# SSOP-TSSOP28.net
KiCad netlist of a schematic drawn in Altium Designer
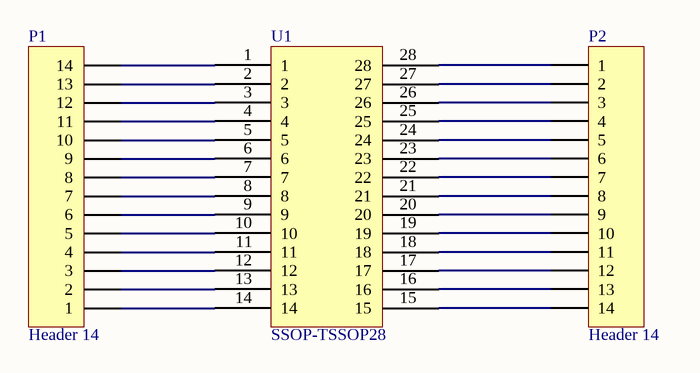
[diagram p0: SSOP-TSSOP28.SchDoc]

(export (version "E")
  (design (tool "Eeschema 10.0.6"))
  (components
    (comp (ref "P1")
      (value "Header 14")
      (footprint "HDR1X14")
      (description "Header, 14-Pin")
      (fields (field (name "PUBLISHER") "Altium Limited"))
      (libsource (lib "Miscellaneous Connectors") (part "Header 14"))
    )
    (comp (ref "P2")
      (value "Header 14")
      (footprint "HDR1X14")
      (description "Header, 14-Pin")
      (fields (field (name "PUBLISHER") "Altium Limited"))
      (libsource (lib "") (part "Header 14_1"))
    )
    (comp (ref "U1")
      (value "SSOP-TSSOP28")
      (footprint "SSOP-TSSOP28")
      (libsource (lib "PCB_Breakout_Boards") (part "SSOP-TSSOP28"))
    )
  )
  (nets
    (net (code "1") (name "Net-(P1-Pad1)") (class "Default")
      (node (ref "P1") (pin "1") (pinfunction "1_1") (pintype "passive"))
      (node (ref "U1") (pin "14") (pinfunction "14_14") (pintype "passive"))
    )
    (net (code "2") (name "Net-(P1-Pad2)") (class "Default")
      (node (ref "P1") (pin "2") (pinfunction "2_2") (pintype "passive"))
      (node (ref "U1") (pin "13") (pinfunction "13_13") (pintype "passive"))
    )
    (net (code "3") (name "Net-(P1-Pad3)") (class "Default")
      (node (ref "P1") (pin "3") (pinfunction "3_3") (pintype "passive"))
      (node (ref "U1") (pin "12") (pinfunction "12_12") (pintype "passive"))
    )
    (net (code "4") (name "Net-(P1-Pad4)") (class "Default")
      (node (ref "P1") (pin "4") (pinfunction "4_4") (pintype "passive"))
      (node (ref "U1") (pin "11") (pinfunction "11_11") (pintype "passive"))
    )
    (net (code "5") (name "Net-(P1-Pad5)") (class "Default")
      (node (ref "P1") (pin "5") (pinfunction "5_5") (pintype "passive"))
      (node (ref "U1") (pin "10") (pinfunction "10_10") (pintype "passive"))
    )
    (net (code "6") (name "Net-(P1-Pad6)") (class "Default")
      (node (ref "P1") (pin "6") (pinfunction "6_6") (pintype "passive"))
      (node (ref "U1") (pin "9") (pinfunction "9_9") (pintype "passive"))
    )
    (net (code "7") (name "Net-(P1-Pad7)") (class "Default")
      (node (ref "P1") (pin "7") (pinfunction "7_7") (pintype "passive"))
      (node (ref "U1") (pin "8") (pinfunction "8_8") (pintype "passive"))
    )
    (net (code "8") (name "Net-(P1-Pad8)") (class "Default")
      (node (ref "P1") (pin "8") (pinfunction "8_8") (pintype "passive"))
      (node (ref "U1") (pin "7") (pinfunction "7_7") (pintype "passive"))
    )
    (net (code "9") (name "Net-(P1-Pad9)") (class "Default")
      (node (ref "P1") (pin "9") (pinfunction "9_9") (pintype "passive"))
      (node (ref "U1") (pin "6") (pinfunction "6_6") (pintype "passive"))
    )
    (net (code "10") (name "Net-(P1-Pad10)") (class "Default")
      (node (ref "P1") (pin "10") (pinfunction "10_10") (pintype "passive"))
      (node (ref "U1") (pin "5") (pinfunction "5_5") (pintype "passive"))
    )
    (net (code "11") (name "Net-(P1-Pad11)") (class "Default")
      (node (ref "P1") (pin "11") (pinfunction "11_11") (pintype "passive"))
      (node (ref "U1") (pin "4") (pinfunction "4_4") (pintype "passive"))
    )
    (net (code "12") (name "Net-(P1-Pad12)") (class "Default")
      (node (ref "P1") (pin "12") (pinfunction "12_12") (pintype "passive"))
      (node (ref "U1") (pin "3") (pinfunction "3_3") (pintype "passive"))
    )
    (net (code "13") (name "Net-(P1-Pad13)") (class "Default")
      (node (ref "P1") (pin "13") (pinfunction "13_13") (pintype "passive"))
      (node (ref "U1") (pin "2") (pinfunction "2_2") (pintype "passive"))
    )
    (net (code "14") (name "Net-(P1-Pad14)") (class "Default")
      (node (ref "P1") (pin "14") (pinfunction "14_14") (pintype "passive"))
      (node (ref "U1") (pin "1") (pinfunction "1_1") (pintype "passive"))
    )
    (net (code "15") (name "Net-(P2-Pad1)") (class "Default")
      (node (ref "P2") (pin "1") (pinfunction "1_1") (pintype "passive"))
      (node (ref "U1") (pin "28") (pinfunction "28_28") (pintype "passive"))
    )
    (net (code "16") (name "Net-(P2-Pad2)") (class "Default")
      (node (ref "P2") (pin "2") (pinfunction "2_2") (pintype "passive"))
      (node (ref "U1") (pin "27") (pinfunction "27_27") (pintype "passive"))
    )
    (net (code "17") (name "Net-(P2-Pad3)") (class "Default")
      (node (ref "P2") (pin "3") (pinfunction "3_3") (pintype "passive"))
      (node (ref "U1") (pin "26") (pinfunction "26_26") (pintype "passive"))
    )
    (net (code "18") (name "Net-(P2-Pad4)") (class "Default")
      (node (ref "P2") (pin "4") (pinfunction "4_4") (pintype "passive"))
      (node (ref "U1") (pin "25") (pinfunction "25_25") (pintype "passive"))
    )
    (net (code "19") (name "Net-(P2-Pad5)") (class "Default")
      (node (ref "P2") (pin "5") (pinfunction "5_5") (pintype "passive"))
      (node (ref "U1") (pin "24") (pinfunction "24_24") (pintype "passive"))
    )
    (net (code "20") (name "Net-(P2-Pad6)") (class "Default")
      (node (ref "P2") (pin "6") (pinfunction "6_6") (pintype "passive"))
      (node (ref "U1") (pin "23") (pinfunction "23_23") (pintype "passive"))
    )
    (net (code "21") (name "Net-(P2-Pad7)") (class "Default")
      (node (ref "P2") (pin "7") (pinfunction "7_7") (pintype "passive"))
      (node (ref "U1") (pin "22") (pinfunction "22_22") (pintype "passive"))
    )
    (net (code "22") (name "Net-(P2-Pad8)") (class "Default")
      (node (ref "P2") (pin "8") (pinfunction "8_8") (pintype "passive"))
      (node (ref "U1") (pin "21") (pinfunction "21_21") (pintype "passive"))
    )
    (net (code "23") (name "Net-(P2-Pad9)") (class "Default")
      (node (ref "P2") (pin "9") (pinfunction "9_9") (pintype "passive"))
      (node (ref "U1") (pin "20") (pinfunction "20_20") (pintype "passive"))
    )
    (net (code "24") (name "Net-(P2-Pad10)") (class "Default")
      (node (ref "P2") (pin "10") (pinfunction "10_10") (pintype "passive"))
      (node (ref "U1") (pin "19") (pinfunction "19_19") (pintype "passive"))
    )
    (net (code "25") (name "Net-(P2-Pad11)") (class "Default")
      (node (ref "P2") (pin "11") (pinfunction "11_11") (pintype "passive"))
      (node (ref "U1") (pin "18") (pinfunction "18_18") (pintype "passive"))
    )
    (net (code "26") (name "Net-(P2-Pad12)") (class "Default")
      (node (ref "P2") (pin "12") (pinfunction "12_12") (pintype "passive"))
      (node (ref "U1") (pin "17") (pinfunction "17_17") (pintype "passive"))
    )
    (net (code "27") (name "Net-(P2-Pad13)") (class "Default")
      (node (ref "P2") (pin "13") (pinfunction "13_13") (pintype "passive"))
      (node (ref "U1") (pin "16") (pinfunction "16_16") (pintype "passive"))
    )
    (net (code "28") (name "Net-(P2-Pad14)") (class "Default")
      (node (ref "P2") (pin "14") (pinfunction "14_14") (pintype "passive"))
      (node (ref "U1") (pin "15") (pinfunction "15_15") (pintype "passive"))
    )
  )
)
